# TriacSwitch2.net
KiCad netlist of a schematic drawn in EAGLE
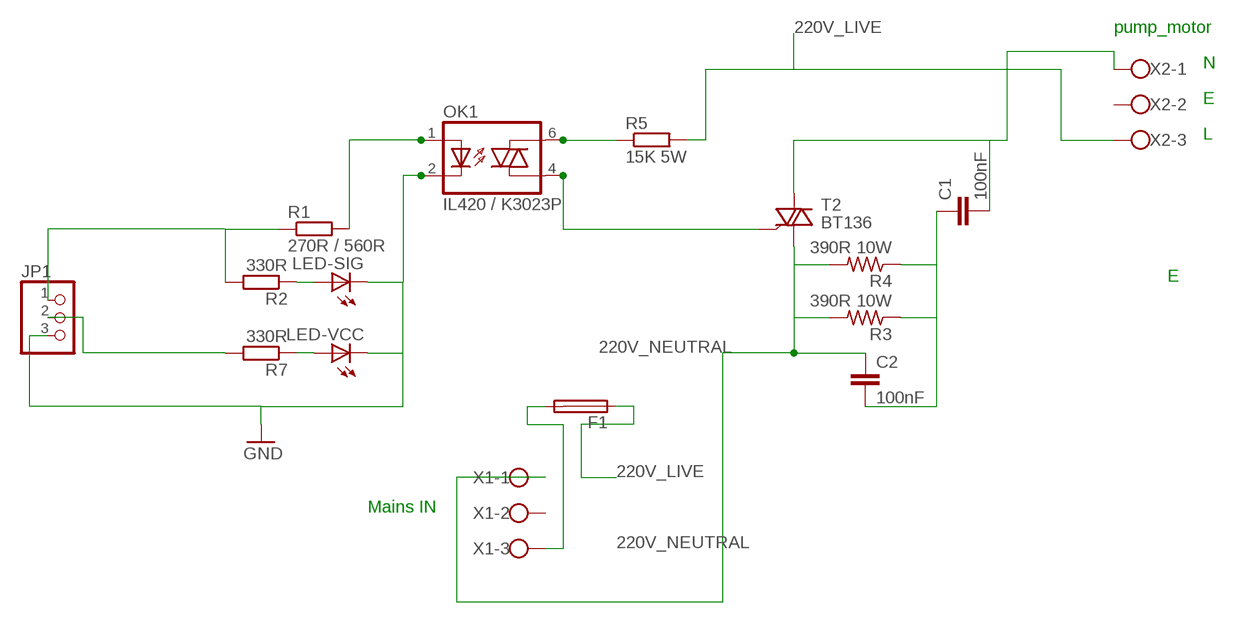
[diagram p0: schematic, sheet 1]

(export (version "E")
  (design (tool "Eeschema 10.0.6"))
  (components
    (comp (ref "C1")
      (value "100nF")
      (footprint "eagle-import:C150-054X183")
      (libsource (lib "eagle-import") (part "C-EU150-054X183"))
    )
    (comp (ref "C2")
      (value "100nF")
      (footprint "eagle-import:C150-054X183")
      (libsource (lib "eagle-import") (part "C-EU150-054X183"))
    )
    (comp (ref "F1")
      (value "GSH15")
      (footprint "eagle-import:GSH15")
      (fields
        (field (name "MPN") "64900001039")
        (field (name "MPN_1") "64900001039")
        (field (name "OC_FARNELL") "1271673")
        (field (name "OC_NEWARK") "02P0318")
      )
      (libsource (lib "eagle-import") (part "GSH15"))
    )
    (comp (ref "JP1")
      (value "PINHD-1X3")
      (footprint "eagle-import:1X03")
      (libsource (lib "eagle-import") (part "PINHD-1X3"))
    )
    (comp (ref "LED-SIG")
      (value "LED3MM")
      (footprint "eagle-import:LED3MM")
      (libsource (lib "eagle-import") (part "LED3MM"))
    )
    (comp (ref "LED-VCC")
      (value "LED3MM")
      (footprint "eagle-import:LED3MM")
      (libsource (lib "eagle-import") (part "LED3MM"))
    )
    (comp (ref "OK1")
      (value "IL420 / K3023P")
      (footprint "eagle-import:DIL06")
      (fields (field (name "MF") "VISHAY/TELEFUNKEN") (field (name "MPN") "IL420"))
      (libsource (lib "eagle-import") (part "IL420"))
    )
    (comp (ref "R1")
      (value "270R / 560R")
      (footprint "eagle-import:0204_7")
      (libsource (lib "eagle-import") (part "R-EU_0204/7"))
    )
    (comp (ref "R2")
      (value "330R")
      (footprint "eagle-import:0204_7")
      (libsource (lib "eagle-import") (part "R-EU_0204/7"))
    )
    (comp (ref "R3")
      (value "390R 10W")
      (footprint "eagle-import:0922_22")
      (libsource (lib "eagle-import") (part "R-US_0922/22"))
    )
    (comp (ref "R4")
      (value "390R 10W")
      (footprint "eagle-import:0922_22")
      (libsource (lib "eagle-import") (part "R-US_0922/22"))
    )
    (comp (ref "R5")
      (value "15K 5W")
      (footprint "eagle-import:0617_22")
      (libsource (lib "eagle-import") (part "R-EU_0617/22"))
    )
    (comp (ref "R7")
      (value "330R")
      (footprint "eagle-import:0204_7")
      (libsource (lib "eagle-import") (part "R-EU_0204/7"))
    )
    (comp (ref "T2")
      (value "BT136")
      (footprint "eagle-import:TO220AB")
      (libsource (lib "eagle-import") (part "BT136"))
    )
    (comp (ref "X1")
      (value "W237-103")
      (footprint "eagle-import:W237-103")
      (fields (field (name "MPN") "237-103"))
      (libsource (lib "eagle-import") (part "W237-103"))
    )
    (comp (ref "X2")
      (value "W237-103")
      (footprint "eagle-import:W237-103")
      (fields (field (name "MPN") "237-103"))
      (libsource (lib "eagle-import") (part "W237-103"))
    )
  )
  (nets
    (net (code "1") (name "/220V_LIVE") (class "Default")
      (node (ref "F1") (pin "1") (pinfunction "1_1") (pintype "passive"))
      (node (ref "R5") (pin "2") (pinfunction "2_2") (pintype "passive"))
      (node (ref "X2") (pin "3") (pinfunction "KL_3") (pintype "passive"))
    )
    (net (code "2") (name "/220V_NEUTRAL") (class "Default")
      (node (ref "C2") (pin "1") (pinfunction "1_1") (pintype "passive"))
      (node (ref "R3") (pin "2") (pinfunction "2_2") (pintype "passive"))
      (node (ref "R4") (pin "2") (pinfunction "2_2") (pintype "passive"))
      (node (ref "T2") (pin "1") (pinfunction "A1_1") (pintype "passive"))
      (node (ref "X1") (pin "1") (pinfunction "KL_1") (pintype "passive"))
    )
    (net (code "3") (name "GND") (class "Default")
      (node (ref "JP1") (pin "3") (pinfunction "3_3") (pintype "passive"))
      (node (ref "LED-SIG") (pin "K") (pinfunction "C_K") (pintype "passive"))
      (node (ref "LED-VCC") (pin "K") (pinfunction "C_K") (pintype "passive"))
      (node (ref "OK1") (pin "2") (pinfunction "C_2") (pintype "passive"))
    )
    (net (code "4") (name "Net-(C1-Pad1)") (class "Default")
      (node (ref "C1") (pin "1") (pinfunction "1_1") (pintype "passive"))
      (node (ref "C2") (pin "2") (pinfunction "2_2") (pintype "passive"))
      (node (ref "R3") (pin "1") (pinfunction "1_1") (pintype "passive"))
      (node (ref "R4") (pin "1") (pinfunction "1_1") (pintype "passive"))
    )
    (net (code "5") (name "Net-(JP1-Pad1)") (class "Default")
      (node (ref "JP1") (pin "1") (pinfunction "1_1") (pintype "passive"))
      (node (ref "R1") (pin "1") (pinfunction "1_1") (pintype "passive"))
      (node (ref "R2") (pin "2") (pinfunction "2_2") (pintype "passive"))
    )
    (net (code "6") (name "Net-(JP1-Pad2)") (class "Default")
      (node (ref "JP1") (pin "2") (pinfunction "2_2") (pintype "passive"))
      (node (ref "R7") (pin "2") (pinfunction "2_2") (pintype "passive"))
    )
    (net (code "7") (name "Net-(LED-SIG-PadA)") (class "Default")
      (node (ref "LED-SIG") (pin "A") (pinfunction "A_A") (pintype "passive"))
      (node (ref "R2") (pin "1") (pinfunction "1_1") (pintype "passive"))
    )
    (net (code "8") (name "Net-(LED-VCC-PadA)") (class "Default")
      (node (ref "LED-VCC") (pin "A") (pinfunction "A_A") (pintype "passive"))
      (node (ref "R7") (pin "1") (pinfunction "1_1") (pintype "passive"))
    )
    (net (code "9") (name "Net-(OK1-A)") (class "Default")
      (node (ref "OK1") (pin "1") (pinfunction "A_1") (pintype "passive"))
      (node (ref "R1") (pin "2") (pinfunction "2_2") (pintype "passive"))
    )
    (net (code "10") (name "Net-(OK1-A1)") (class "Default")
      (node (ref "OK1") (pin "4") (pinfunction "A1_4") (pintype "passive"))
      (node (ref "T2") (pin "3") (pinfunction "G_3") (pintype "passive"))
    )
    (net (code "11") (name "Net-(OK1-A2)") (class "Default")
      (node (ref "OK1") (pin "6") (pinfunction "A2_6") (pintype "passive"))
      (node (ref "R5") (pin "1") (pinfunction "1_1") (pintype "passive"))
    )
    (net (code "12") (name "Net-(T2-A2)") (class "Default")
      (node (ref "C1") (pin "2") (pinfunction "2_2") (pintype "passive"))
      (node (ref "T2") (pin "2") (pinfunction "A2_2") (pintype "passive"))
      (node (ref "X2") (pin "1") (pinfunction "KL_1") (pintype "passive"))
    )
    (net (code "13") (name "Net-(X1C-KL)") (class "Default")
      (node (ref "F1") (pin "2") (pinfunction "2_2") (pintype "passive"))
      (node (ref "X1") (pin "3") (pinfunction "KL_3") (pintype "passive"))
    )
    (net (code "14") (name "unconnected-(X1B-KL-Pad2)") (class "Default")
      (node (ref "X1") (pin "2") (pinfunction "KL_2") (pintype "passive"))
    )
    (net (code "15") (name "unconnected-(X2B-KL-Pad2)") (class "Default")
      (node (ref "X2") (pin "2") (pinfunction "KL_2") (pintype "passive"))
    )
  )
)
